# DRV8825_stepper_motor_controller.net
KiCad netlist of a schematic drawn in Altium Designer
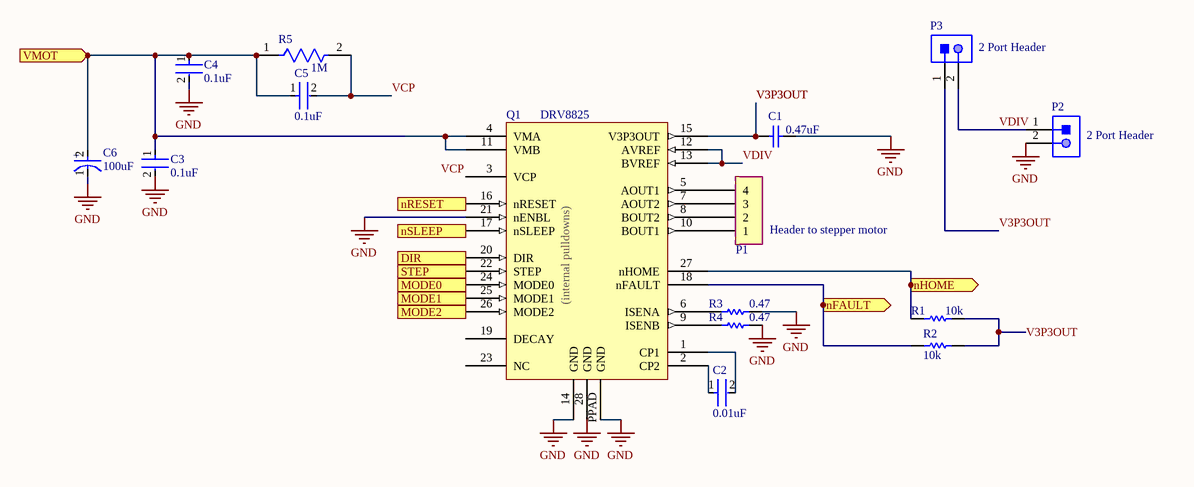
[diagram p0: DRV8825 stepper motor controller.SchDoc]

(export (version "E")
  (design (tool "Eeschema 10.0.6"))
  (components
    (comp (ref "C1")
      (value "0.47uF")
      (footprint "CAPC2013X140X50ML20T25")
      (fields (field (name "PART NUMBER") "C0805F474K3RACTU") (field (name "MANUFACTURER") "Kemet"))
      (libsource (lib "Altium Content Vault") (part "CAP"))
    )
    (comp (ref "C2")
      (value "0.01uF")
      (footprint "FP-0805-L_2_01_0_2-W_1_25-IPC_B")
      (description "General Purpose Ceramic Capacitor, 0805, 10nF, 5%, X7R, 0.15, 50V")
      (fields (field (name "VOLTAGE") "50V") (field (name "TOLERANCE") "5%"))
      (libsource (lib "Altium Content Vault") (part "02cd4be3c70576c341d710602a673aa"))
    )
    (comp (ref "C3")
      (value "0.1uF")
      (footprint "FP-0805-L_2_01_0_2-W_1_25-IPC_C")
      (description "General Purpose Ceramic Capacitor, 0805, 100nF, 10%, X7R, 0.15, 50V")
      (fields (field (name "TOLERANCE") "10%") (field (name "VOLTAGE") "50V"))
      (libsource (lib "Altium Content Vault") (part "02cd4be3c70576c341d710602a673aa"))
    )
    (comp (ref "C4")
      (value "0.1uF")
      (footprint "FP-0805-L_2_01_0_2-W_1_25-IPC_C")
      (description "General Purpose Ceramic Capacitor, 0805, 100nF, 10%, X7R, 0.15, 50V")
      (fields (field (name "TOLERANCE") "10%") (field (name "VOLTAGE") "50V"))
      (libsource (lib "Altium Content Vault") (part "02cd4be3c70576c341d710602a673aa"))
    )
    (comp (ref "C5")
      (value "0.1uF")
      (footprint "FP-0805-L_2_01_0_2-W_1_25-IPC_C")
      (description "General Purpose Ceramic Capacitor, 0805, 100nF, 10%, X7R, 0.15, 50V")
      (fields (field (name "TOLERANCE") "10%") (field (name "VOLTAGE") "50V"))
      (libsource (lib "Altium Content Vault") (part "02cd4be3c70576c341d710602a673aa"))
    )
    (comp (ref "C6")
      (value "100uF")
      (footprint "FP-FKE-MFG")
      (description "CAP ALUM 100UF 20% 25V SMD")
      (fields (field (name "TOLERANCE") "20%") (field (name "VOLTAGE") "25V"))
      (libsource (lib "Altium Content Vault") (part "203bc49f2ac43e59fd269a8c329ed05"))
    )
    (comp (ref "P1")
      (value "Header to stepper motor")
      (footprint "B4B-XH-A (LF)(SN)")
      (description "Wire-to-board connector, vertical, 2.5mm, 4 contacts")
      (libsource (lib "JCULibrary_AS2_v2") (part "B4B-XH-A (LF)(SN) Wire-to-board connector"))
    )
    (comp (ref "P2")
      (value "2 Port Header")
      (footprint "JST-B2P-VH(LF)(SN)_V")
      (fields (field (name "TOLERANCE") "5%"))
      (libsource (lib "") (part "JST_B2P-VH(LF)(SN)_1"))
    )
    (comp (ref "P3")
      (value "2 Port Header")
      (footprint "JST-B2P-VH(LF)(SN)_V")
      (fields (field (name "TOLERANCE") "5%"))
      (libsource (lib "JCULibrary_AS2_v2") (part "JST_B2P-VH(LF)(SN)"))
    )
    (comp (ref "Q1")
      (value "DRV8825")
      (footprint "DRV8825 HTSSOP")
      (description "TI DRV8825 Stepper Motor Controller IC")
      (libsource (lib "JCULibrary_AS2_v2") (part "Stepper motor driver DRV8825"))
    )
    (comp (ref "R1")
      (value "10k")
      (footprint "RESC2013X60X35ML10T20")
      (description "Chip Resistor, 10 KOhm, +/- 5%, 0.125 W, -55 to 155 degC, 0805 (2012 Metric), RoHS, Tape and Reel")
      (fields (field (name "MANUFACTURER") "Yageo"))
      (libsource (lib "Altium Content Vault") (part "RES-2"))
    )
    (comp (ref "R2")
      (value "10k")
      (footprint "RESC2013X60X35ML10T20")
      (description "Chip Resistor, 10 KOhm, +/- 5%, 0.125 W, -55 to 155 degC, 0805 (2012 Metric), RoHS, Tape and Reel")
      (fields (field (name "MANUFACTURER") "Yageo"))
      (libsource (lib "Altium Content Vault") (part "RES-2"))
    )
    (comp (ref "R3")
      (value "0.47")
      (footprint "RESC2013X65X40ML15T20")
      (fields (field (name "PART NUMBER") "RCWE0805R470FKEA") (field (name "MANUFACTURER") "Vishay Dale"))
      (libsource (lib "Altium Content Vault") (part "RES"))
    )
    (comp (ref "R4")
      (value "0.47")
      (footprint "RESC2013X65X40ML15T20")
      (fields (field (name "PART NUMBER") "RCWE0805R470FKEA") (field (name "MANUFACTURER") "Vishay Dale"))
      (libsource (lib "Altium Content Vault") (part "RES"))
    )
    (comp (ref "R5")
      (value "1M")
      (footprint "FP-CRCW0805-e3-IPC_B")
      (description "RES Thick Film, 1MΩ, 1%, 0.125W, 100ppm/°C, 0805")
      (fields (field (name "TOLERANCE") "1%"))
      (libsource (lib "Altium Content Vault") (part "1029c3af85768c4190bb7ad29bc67b5"))
    )
  )
  (nets
    (net (code "1") (name "/DIR") (class "Default")
      (node (ref "Q1") (pin "20") (pinfunction "DIR_20") (pintype "input"))
    )
    (net (code "2") (name "/MODE0") (class "Default")
      (node (ref "Q1") (pin "24") (pinfunction "MODE0_24") (pintype "input"))
    )
    (net (code "3") (name "/MODE1") (class "Default")
      (node (ref "Q1") (pin "25") (pinfunction "MODE1_25") (pintype "input"))
    )
    (net (code "4") (name "/MODE2") (class "Default")
      (node (ref "Q1") (pin "26") (pinfunction "MODE2_26") (pintype "input"))
    )
    (net (code "5") (name "/STEP") (class "Default")
      (node (ref "Q1") (pin "22") (pinfunction "STEP_22") (pintype "input"))
    )
    (net (code "6") (name "/V3P3OUT") (class "Default")
      (node (ref "C1") (pin "1") (pinfunction "1_1") (pintype "passive"))
      (node (ref "P3") (pin "1") (pinfunction "1_1") (pintype "passive"))
      (node (ref "Q1") (pin "15") (pinfunction "V3P3OUT_15") (pintype "output"))
      (node (ref "R1") (pin "2") (pinfunction "2_2") (pintype "passive"))
      (node (ref "R2") (pin "1") (pinfunction "1_1") (pintype "passive"))
    )
    (net (code "7") (name "/VCP") (class "Default")
      (node (ref "C5") (pin "2") (pinfunction "2_2") (pintype "passive"))
      (node (ref "Q1") (pin "3") (pinfunction "VCP_3") (pintype "power_in"))
      (node (ref "R5") (pin "2") (pinfunction "2_2") (pintype "passive"))
    )
    (net (code "8") (name "/VDIV") (class "Default")
      (node (ref "P2") (pin "1") (pinfunction "1_1") (pintype "passive"))
      (node (ref "P3") (pin "2") (pinfunction "2_2") (pintype "passive"))
      (node (ref "Q1") (pin "12") (pinfunction "AVREF_12") (pintype "input"))
      (node (ref "Q1") (pin "13") (pinfunction "BVREF_13") (pintype "input"))
    )
    (net (code "9") (name "/VMOT") (class "Default")
      (node (ref "C3") (pin "1") (pinfunction "1_1") (pintype "passive"))
      (node (ref "C4") (pin "1") (pinfunction "1_1") (pintype "passive"))
      (node (ref "C5") (pin "1") (pinfunction "1_1") (pintype "passive"))
      (node (ref "C6") (pin "2") (pinfunction "A_2") (pintype "passive"))
      (node (ref "Q1") (pin "11") (pinfunction "VMB_11") (pintype "power_in"))
      (node (ref "Q1") (pin "4") (pinfunction "VMA_4") (pintype "power_in"))
      (node (ref "R5") (pin "1") (pinfunction "1_1") (pintype "passive"))
    )
    (net (code "10") (name "/nFAULT") (class "Default")
      (node (ref "Q1") (pin "18") (pinfunction "nFAULT_18") (pintype "open_collector"))
      (node (ref "R2") (pin "2") (pinfunction "2_2") (pintype "passive"))
    )
    (net (code "11") (name "/nHOME") (class "Default")
      (node (ref "Q1") (pin "27") (pinfunction "nHOME_27") (pintype "open_collector"))
      (node (ref "R1") (pin "1") (pinfunction "1_1") (pintype "passive"))
    )
    (net (code "12") (name "/nRESET") (class "Default")
      (node (ref "Q1") (pin "16") (pinfunction "nRESET_16") (pintype "input"))
    )
    (net (code "13") (name "/nSLEEP") (class "Default")
      (node (ref "Q1") (pin "17") (pinfunction "nSLEEP_17") (pintype "input"))
    )
    (net (code "14") (name "GND") (class "Default")
      (node (ref "C1") (pin "2") (pinfunction "2_2") (pintype "passive"))
      (node (ref "C3") (pin "2") (pinfunction "2_2") (pintype "passive"))
      (node (ref "C4") (pin "2") (pinfunction "2_2") (pintype "passive"))
      (node (ref "C6") (pin "1") (pinfunction "C_1") (pintype "passive"))
      (node (ref "P2") (pin "2") (pinfunction "2_2") (pintype "passive"))
      (node (ref "Q1") (pin "14") (pinfunction "GND_14") (pintype "power_in"))
      (node (ref "Q1") (pin "21") (pinfunction "nENBL_21") (pintype "input"))
      (node (ref "Q1") (pin "28") (pinfunction "GND_28") (pintype "power_in"))
      (node (ref "Q1") (pin "PPAD") (pinfunction "GND_PPAD") (pintype "power_in"))
      (node (ref "R3") (pin "2") (pinfunction "2_2") (pintype "passive"))
      (node (ref "R4") (pin "2") (pinfunction "2_2") (pintype "passive"))
    )
    (net (code "15") (name "Net-(Q1-AOUT1)") (class "Default")
      (node (ref "P1") (pin "4") (pinfunction "4_4") (pintype "passive"))
      (node (ref "Q1") (pin "5") (pinfunction "AOUT1_5") (pintype "output"))
    )
    (net (code "16") (name "Net-(Q1-AOUT2)") (class "Default")
      (node (ref "P1") (pin "3") (pinfunction "3_3") (pintype "passive"))
      (node (ref "Q1") (pin "7") (pinfunction "AOUT2_7") (pintype "output"))
    )
    (net (code "17") (name "Net-(Q1-BOUT1)") (class "Default")
      (node (ref "P1") (pin "1") (pinfunction "1_1") (pintype "passive"))
      (node (ref "Q1") (pin "10") (pinfunction "BOUT1_10") (pintype "output"))
    )
    (net (code "18") (name "Net-(Q1-BOUT2)") (class "Default")
      (node (ref "P1") (pin "2") (pinfunction "2_2") (pintype "passive"))
      (node (ref "Q1") (pin "8") (pinfunction "BOUT2_8") (pintype "output"))
    )
    (net (code "19") (name "Net-(Q1-CP1)") (class "Default")
      (node (ref "C2") (pin "2") (pinfunction "2_2") (pintype "passive"))
      (node (ref "Q1") (pin "1") (pinfunction "CP1_1") (pintype "power_in"))
    )
    (net (code "20") (name "Net-(Q1-CP2)") (class "Default")
      (node (ref "C2") (pin "1") (pinfunction "1_1") (pintype "passive"))
      (node (ref "Q1") (pin "2") (pinfunction "CP2_2") (pintype "power_in"))
    )
    (net (code "21") (name "Net-(Q1-ISENA)") (class "Default")
      (node (ref "Q1") (pin "6") (pinfunction "ISENA_6") (pintype "output"))
      (node (ref "R3") (pin "1") (pinfunction "1_1") (pintype "passive"))
    )
    (net (code "22") (name "Net-(Q1-ISENB)") (class "Default")
      (node (ref "Q1") (pin "9") (pinfunction "ISENB_9") (pintype "output"))
      (node (ref "R4") (pin "1") (pinfunction "1_1") (pintype "passive"))
    )
    (net (code "23") (name "unconnected-(Q1-DECAY-Pad19)") (class "Default")
      (node (ref "Q1") (pin "19") (pinfunction "DECAY_19") (pintype "passive"))
    )
    (net (code "24") (name "unconnected-(Q1-NC-Pad23)") (class "Default")
      (node (ref "Q1") (pin "23") (pinfunction "NC_23") (pintype "passive"))
    )
  )
)
